# tda.net
KiCad netlist of a schematic drawn in EAGLE
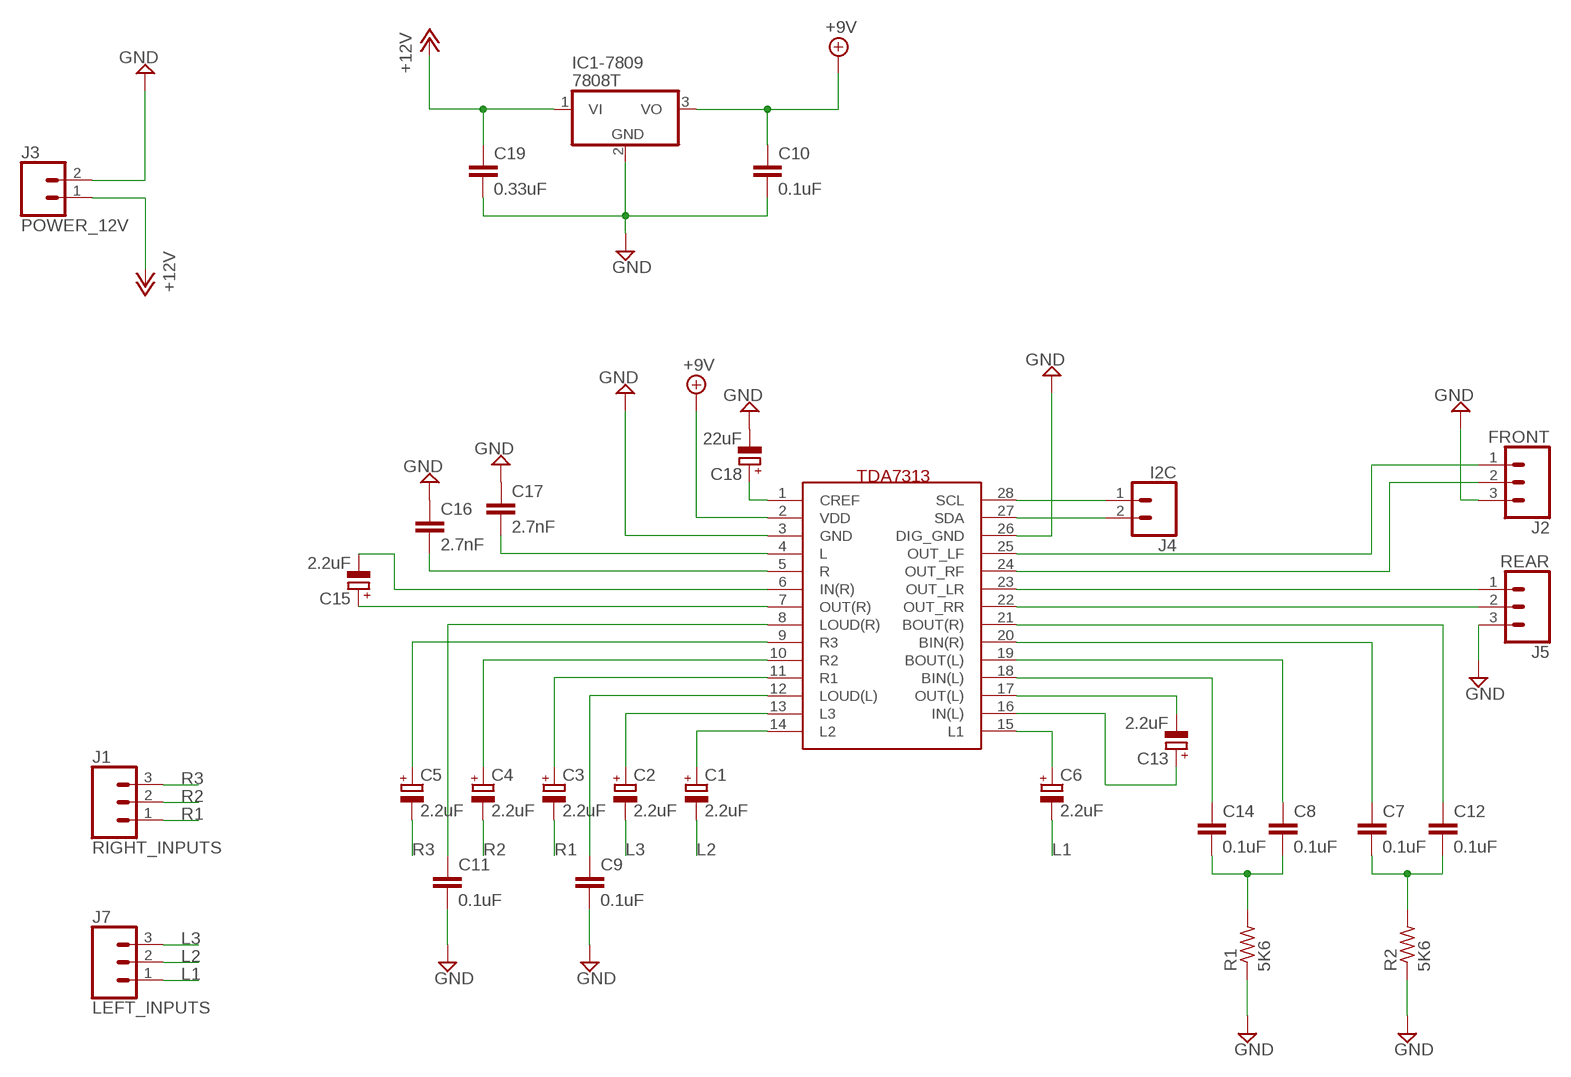
[diagram p0: schematic, sheet 1]

(export (version "E")
  (design (tool "Eeschema 10.0.6"))
  (components
    (comp (ref "C1")
      (value "2.2uF")
      (footprint "eagle-import:E2-4")
      (libsource (lib "eagle-import") (part "CPOL-EUE2-4"))
    )
    (comp (ref "C2")
      (value "2.2uF")
      (footprint "eagle-import:E2-4")
      (libsource (lib "eagle-import") (part "CPOL-EUE2-4"))
    )
    (comp (ref "C3")
      (value "2.2uF")
      (footprint "eagle-import:E2-4")
      (libsource (lib "eagle-import") (part "CPOL-EUE2-4"))
    )
    (comp (ref "C4")
      (value "2.2uF")
      (footprint "eagle-import:E2-4")
      (libsource (lib "eagle-import") (part "CPOL-EUE2-4"))
    )
    (comp (ref "C5")
      (value "2.2uF")
      (footprint "eagle-import:E2-4")
      (libsource (lib "eagle-import") (part "CPOL-EUE2-4"))
    )
    (comp (ref "C6")
      (value "2.2uF")
      (footprint "eagle-import:E2-4")
      (libsource (lib "eagle-import") (part "CPOL-EUE2-4"))
    )
    (comp (ref "C7")
      (value "0.1uF")
      (footprint "eagle-import:C0805")
      (libsource (lib "eagle-import") (part "C-EUC0805"))
    )
    (comp (ref "C8")
      (value "0.1uF")
      (footprint "eagle-import:C0805")
      (libsource (lib "eagle-import") (part "C-EUC0805"))
    )
    (comp (ref "C9")
      (value "0.1uF")
      (footprint "eagle-import:C0805")
      (libsource (lib "eagle-import") (part "C-EUC0805"))
    )
    (comp (ref "C10")
      (value "0.1uF")
      (footprint "eagle-import:C0805")
      (libsource (lib "eagle-import") (part "C-EUC0805"))
    )
    (comp (ref "C11")
      (value "0.1uF")
      (footprint "eagle-import:C0805")
      (libsource (lib "eagle-import") (part "C-EUC0805"))
    )
    (comp (ref "C12")
      (value "0.1uF")
      (footprint "eagle-import:C0805")
      (libsource (lib "eagle-import") (part "C-EUC0805"))
    )
    (comp (ref "C13")
      (value "2.2uF")
      (footprint "eagle-import:E2-4")
      (libsource (lib "eagle-import") (part "CPOL-EUE2-4"))
    )
    (comp (ref "C14")
      (value "0.1uF")
      (footprint "eagle-import:C0805")
      (libsource (lib "eagle-import") (part "C-EUC0805"))
    )
    (comp (ref "C15")
      (value "2.2uF")
      (footprint "eagle-import:E2-4")
      (libsource (lib "eagle-import") (part "CPOL-EUE2-4"))
    )
    (comp (ref "C16")
      (value "2.7nF")
      (footprint "eagle-import:C0805")
      (libsource (lib "eagle-import") (part "C-EUC0805"))
    )
    (comp (ref "C17")
      (value "2.7nF")
      (footprint "eagle-import:C0805")
      (libsource (lib "eagle-import") (part "C-EUC0805"))
    )
    (comp (ref "C18")
      (value "22uF")
      (footprint "eagle-import:E2-4")
      (libsource (lib "eagle-import") (part "CPOL-EUE2-4"))
    )
    (comp (ref "C19")
      (value "0.33uF")
      (footprint "eagle-import:C0805")
      (libsource (lib "eagle-import") (part "C-EUC0805"))
    )
    (comp (ref "IC1-7809")
      (value "7808T")
      (footprint "eagle-import:TO220H")
      (libsource (lib "eagle-import") (part "78T08"))
    )
    (comp (ref "J1")
      (value "RIGHT_INPUTS")
      (footprint "eagle-import:1X03_LONGPADS")
      (libsource (lib "eagle-import") (part "CONN_03LONGPADS"))
    )
    (comp (ref "J2")
      (value "FRONT")
      (footprint "eagle-import:1X03_LONGPADS")
      (libsource (lib "eagle-import") (part "CONN_03LONGPADS"))
    )
    (comp (ref "J3")
      (value "POWER_12V")
      (footprint "eagle-import:1X02_LOCK_LONGPADS")
      (libsource (lib "eagle-import") (part "CONN_02LOCK_LONGPADS"))
    )
    (comp (ref "J4")
      (value "I2C")
      (footprint "eagle-import:1X02_LOCK_LONGPADS")
      (libsource (lib "eagle-import") (part "CONN_02LOCK_LONGPADS"))
    )
    (comp (ref "J5")
      (value "REAR")
      (footprint "eagle-import:1X03_LONGPADS")
      (libsource (lib "eagle-import") (part "CONN_03LONGPADS"))
    )
    (comp (ref "J7")
      (value "LEFT_INPUTS")
      (footprint "eagle-import:1X03_LONGPADS")
      (libsource (lib "eagle-import") (part "CONN_03LONGPADS"))
    )
    (comp (ref "R1")
      (value "5K6")
      (footprint "eagle-import:0207_10")
      (libsource (lib "eagle-import") (part "R-US_0207/10"))
    )
    (comp (ref "R2")
      (value "5K6")
      (footprint "eagle-import:0207_10")
      (libsource (lib "eagle-import") (part "R-US_0207/10"))
    )
    (comp (ref "U$1")
      (value "TDA7313_SO28")
      (footprint "eagle-import:SO28")
      (libsource (lib "eagle-import") (part "TDA7313_SO28"))
    )
  )
  (nets
    (net (code "1") (name "+9V") (class "Default")
      (node (ref "C10") (pin "1") (pinfunction "1_1") (pintype "passive"))
      (node (ref "IC1-7809") (pin "3") (pinfunction "VO_3") (pintype "passive"))
      (node (ref "U$1") (pin "2") (pinfunction "VDD_2") (pintype "bidirectional"))
    )
    (net (code "2") (name "+12V") (class "Default")
      (node (ref "C19") (pin "1") (pinfunction "1_1") (pintype "passive"))
      (node (ref "IC1-7809") (pin "1") (pinfunction "VI_1") (pintype "input"))
      (node (ref "J3") (pin "1") (pinfunction "1_1") (pintype "passive"))
    )
    (net (code "3") (name "/L1") (class "Default")
      (node (ref "C6") (pin "-") (pinfunction "-_-") (pintype "passive"))
      (node (ref "J7") (pin "1") (pinfunction "1_1") (pintype "passive"))
    )
    (net (code "4") (name "/L2") (class "Default")
      (node (ref "C1") (pin "-") (pinfunction "-_-") (pintype "passive"))
      (node (ref "J7") (pin "2") (pinfunction "2_2") (pintype "passive"))
    )
    (net (code "5") (name "/L3") (class "Default")
      (node (ref "C2") (pin "-") (pinfunction "-_-") (pintype "passive"))
      (node (ref "J7") (pin "3") (pinfunction "3_3") (pintype "passive"))
    )
    (net (code "6") (name "/R1") (class "Default")
      (node (ref "C3") (pin "-") (pinfunction "-_-") (pintype "passive"))
      (node (ref "J1") (pin "1") (pinfunction "1_1") (pintype "passive"))
    )
    (net (code "7") (name "/R2") (class "Default")
      (node (ref "C4") (pin "-") (pinfunction "-_-") (pintype "passive"))
      (node (ref "J1") (pin "2") (pinfunction "2_2") (pintype "passive"))
    )
    (net (code "8") (name "/R3") (class "Default")
      (node (ref "C5") (pin "-") (pinfunction "-_-") (pintype "passive"))
      (node (ref "J1") (pin "3") (pinfunction "3_3") (pintype "passive"))
    )
    (net (code "9") (name "GND") (class "Default")
      (node (ref "C10") (pin "2") (pinfunction "2_2") (pintype "passive"))
      (node (ref "C11") (pin "2") (pinfunction "2_2") (pintype "passive"))
      (node (ref "C16") (pin "1") (pinfunction "1_1") (pintype "passive"))
      (node (ref "C17") (pin "1") (pinfunction "1_1") (pintype "passive"))
      (node (ref "C18") (pin "-") (pinfunction "-_-") (pintype "passive"))
      (node (ref "C19") (pin "2") (pinfunction "2_2") (pintype "passive"))
      (node (ref "C9") (pin "2") (pinfunction "2_2") (pintype "passive"))
      (node (ref "IC1-7809") (pin "2") (pinfunction "GND_2") (pintype "passive"))
      (node (ref "J2") (pin "3") (pinfunction "3_3") (pintype "passive"))
      (node (ref "J3") (pin "2") (pinfunction "2_2") (pintype "passive"))
      (node (ref "J5") (pin "3") (pinfunction "3_3") (pintype "passive"))
      (node (ref "R1") (pin "1") (pinfunction "1_1") (pintype "passive"))
      (node (ref "R2") (pin "1") (pinfunction "1_1") (pintype "passive"))
      (node (ref "U$1") (pin "26") (pinfunction "DIG_GND_26") (pintype "bidirectional"))
      (node (ref "U$1") (pin "3") (pinfunction "GND_3") (pintype "bidirectional"))
    )
    (net (code "10") (name "Net-(C12-Pad2)") (class "Default")
      (node (ref "C12") (pin "2") (pinfunction "2_2") (pintype "passive"))
      (node (ref "C7") (pin "2") (pinfunction "2_2") (pintype "passive"))
      (node (ref "R2") (pin "2") (pinfunction "2_2") (pintype "passive"))
    )
    (net (code "11") (name "Net-(C14-Pad2)") (class "Default")
      (node (ref "C14") (pin "2") (pinfunction "2_2") (pintype "passive"))
      (node (ref "C8") (pin "2") (pinfunction "2_2") (pintype "passive"))
      (node (ref "R1") (pin "2") (pinfunction "2_2") (pintype "passive"))
    )
    (net (code "12") (name "Net-(U$1-BIN(L))") (class "Default")
      (node (ref "C14") (pin "1") (pinfunction "1_1") (pintype "passive"))
      (node (ref "U$1") (pin "18") (pinfunction "BIN(L)_18") (pintype "bidirectional"))
    )
    (net (code "13") (name "Net-(U$1-BIN(R))") (class "Default")
      (node (ref "C7") (pin "1") (pinfunction "1_1") (pintype "passive"))
      (node (ref "U$1") (pin "20") (pinfunction "BIN(R)_20") (pintype "bidirectional"))
    )
    (net (code "14") (name "Net-(U$1-BOUT(L))") (class "Default")
      (node (ref "C8") (pin "1") (pinfunction "1_1") (pintype "passive"))
      (node (ref "U$1") (pin "19") (pinfunction "BOUT(L)_19") (pintype "bidirectional"))
    )
    (net (code "15") (name "Net-(U$1-BOUT(R))") (class "Default")
      (node (ref "C12") (pin "1") (pinfunction "1_1") (pintype "passive"))
      (node (ref "U$1") (pin "21") (pinfunction "BOUT(R)_21") (pintype "bidirectional"))
    )
    (net (code "16") (name "Net-(U$1-CREF)") (class "Default")
      (node (ref "C18") (pin "+") (pinfunction "+_+") (pintype "passive"))
      (node (ref "U$1") (pin "1") (pinfunction "CREF_1") (pintype "bidirectional"))
    )
    (net (code "17") (name "Net-(U$1-IN(L))") (class "Default")
      (node (ref "C13") (pin "+") (pinfunction "+_+") (pintype "passive"))
      (node (ref "U$1") (pin "16") (pinfunction "IN(L)_16") (pintype "bidirectional"))
    )
    (net (code "18") (name "Net-(U$1-IN(R))") (class "Default")
      (node (ref "C15") (pin "-") (pinfunction "-_-") (pintype "passive"))
      (node (ref "U$1") (pin "6") (pinfunction "IN(R)_6") (pintype "bidirectional"))
    )
    (net (code "19") (name "Net-(U$1-L)") (class "Default")
      (node (ref "C17") (pin "2") (pinfunction "2_2") (pintype "passive"))
      (node (ref "U$1") (pin "4") (pinfunction "L_4") (pintype "bidirectional"))
    )
    (net (code "20") (name "Net-(U$1-L1)") (class "Default")
      (node (ref "C6") (pin "+") (pinfunction "+_+") (pintype "passive"))
      (node (ref "U$1") (pin "15") (pinfunction "L1_15") (pintype "bidirectional"))
    )
    (net (code "21") (name "Net-(U$1-L2)") (class "Default")
      (node (ref "C1") (pin "+") (pinfunction "+_+") (pintype "passive"))
      (node (ref "U$1") (pin "14") (pinfunction "L2_14") (pintype "bidirectional"))
    )
    (net (code "22") (name "Net-(U$1-L3)") (class "Default")
      (node (ref "C2") (pin "+") (pinfunction "+_+") (pintype "passive"))
      (node (ref "U$1") (pin "13") (pinfunction "L3_13") (pintype "bidirectional"))
    )
    (net (code "23") (name "Net-(U$1-LOUD(L))") (class "Default")
      (node (ref "C9") (pin "1") (pinfunction "1_1") (pintype "passive"))
      (node (ref "U$1") (pin "12") (pinfunction "LOUD(L)_12") (pintype "bidirectional"))
    )
    (net (code "24") (name "Net-(U$1-LOUD(R))") (class "Default")
      (node (ref "C11") (pin "1") (pinfunction "1_1") (pintype "passive"))
      (node (ref "U$1") (pin "8") (pinfunction "LOUD(R)_8") (pintype "bidirectional"))
    )
    (net (code "25") (name "Net-(U$1-OUT(L))") (class "Default")
      (node (ref "C13") (pin "-") (pinfunction "-_-") (pintype "passive"))
      (node (ref "U$1") (pin "17") (pinfunction "OUT(L)_17") (pintype "bidirectional"))
    )
    (net (code "26") (name "Net-(U$1-OUT(R))") (class "Default")
      (node (ref "C15") (pin "+") (pinfunction "+_+") (pintype "passive"))
      (node (ref "U$1") (pin "7") (pinfunction "OUT(R)_7") (pintype "bidirectional"))
    )
    (net (code "27") (name "Net-(U$1-OUT_LF)") (class "Default")
      (node (ref "J2") (pin "1") (pinfunction "1_1") (pintype "passive"))
      (node (ref "U$1") (pin "25") (pinfunction "OUT_LF_25") (pintype "bidirectional"))
    )
    (net (code "28") (name "Net-(U$1-OUT_LR)") (class "Default")
      (node (ref "J5") (pin "1") (pinfunction "1_1") (pintype "passive"))
      (node (ref "U$1") (pin "23") (pinfunction "OUT_LR_23") (pintype "bidirectional"))
    )
    (net (code "29") (name "Net-(U$1-OUT_RF)") (class "Default")
      (node (ref "J2") (pin "2") (pinfunction "2_2") (pintype "passive"))
      (node (ref "U$1") (pin "24") (pinfunction "OUT_RF_24") (pintype "bidirectional"))
    )
    (net (code "30") (name "Net-(U$1-OUT_RR)") (class "Default")
      (node (ref "J5") (pin "2") (pinfunction "2_2") (pintype "passive"))
      (node (ref "U$1") (pin "22") (pinfunction "OUT_RR_22") (pintype "bidirectional"))
    )
    (net (code "31") (name "Net-(U$1-R)") (class "Default")
      (node (ref "C16") (pin "2") (pinfunction "2_2") (pintype "passive"))
      (node (ref "U$1") (pin "5") (pinfunction "R_5") (pintype "bidirectional"))
    )
    (net (code "32") (name "Net-(U$1-R1)") (class "Default")
      (node (ref "C3") (pin "+") (pinfunction "+_+") (pintype "passive"))
      (node (ref "U$1") (pin "11") (pinfunction "R1_11") (pintype "bidirectional"))
    )
    (net (code "33") (name "Net-(U$1-R2)") (class "Default")
      (node (ref "C4") (pin "+") (pinfunction "+_+") (pintype "passive"))
      (node (ref "U$1") (pin "10") (pinfunction "R2_10") (pintype "bidirectional"))
    )
    (net (code "34") (name "Net-(U$1-R3)") (class "Default")
      (node (ref "C5") (pin "+") (pinfunction "+_+") (pintype "passive"))
      (node (ref "U$1") (pin "9") (pinfunction "R3_9") (pintype "bidirectional"))
    )
    (net (code "35") (name "Net-(U$1-SCL)") (class "Default")
      (node (ref "J4") (pin "1") (pinfunction "1_1") (pintype "passive"))
      (node (ref "U$1") (pin "28") (pinfunction "SCL_28") (pintype "bidirectional"))
    )
    (net (code "36") (name "Net-(U$1-SDA)") (class "Default")
      (node (ref "J4") (pin "2") (pinfunction "2_2") (pintype "passive"))
      (node (ref "U$1") (pin "27") (pinfunction "SDA_27") (pintype "bidirectional"))
    )
  )
)
